# V_6.net
KiCad netlist of a schematic drawn in Altium Designer
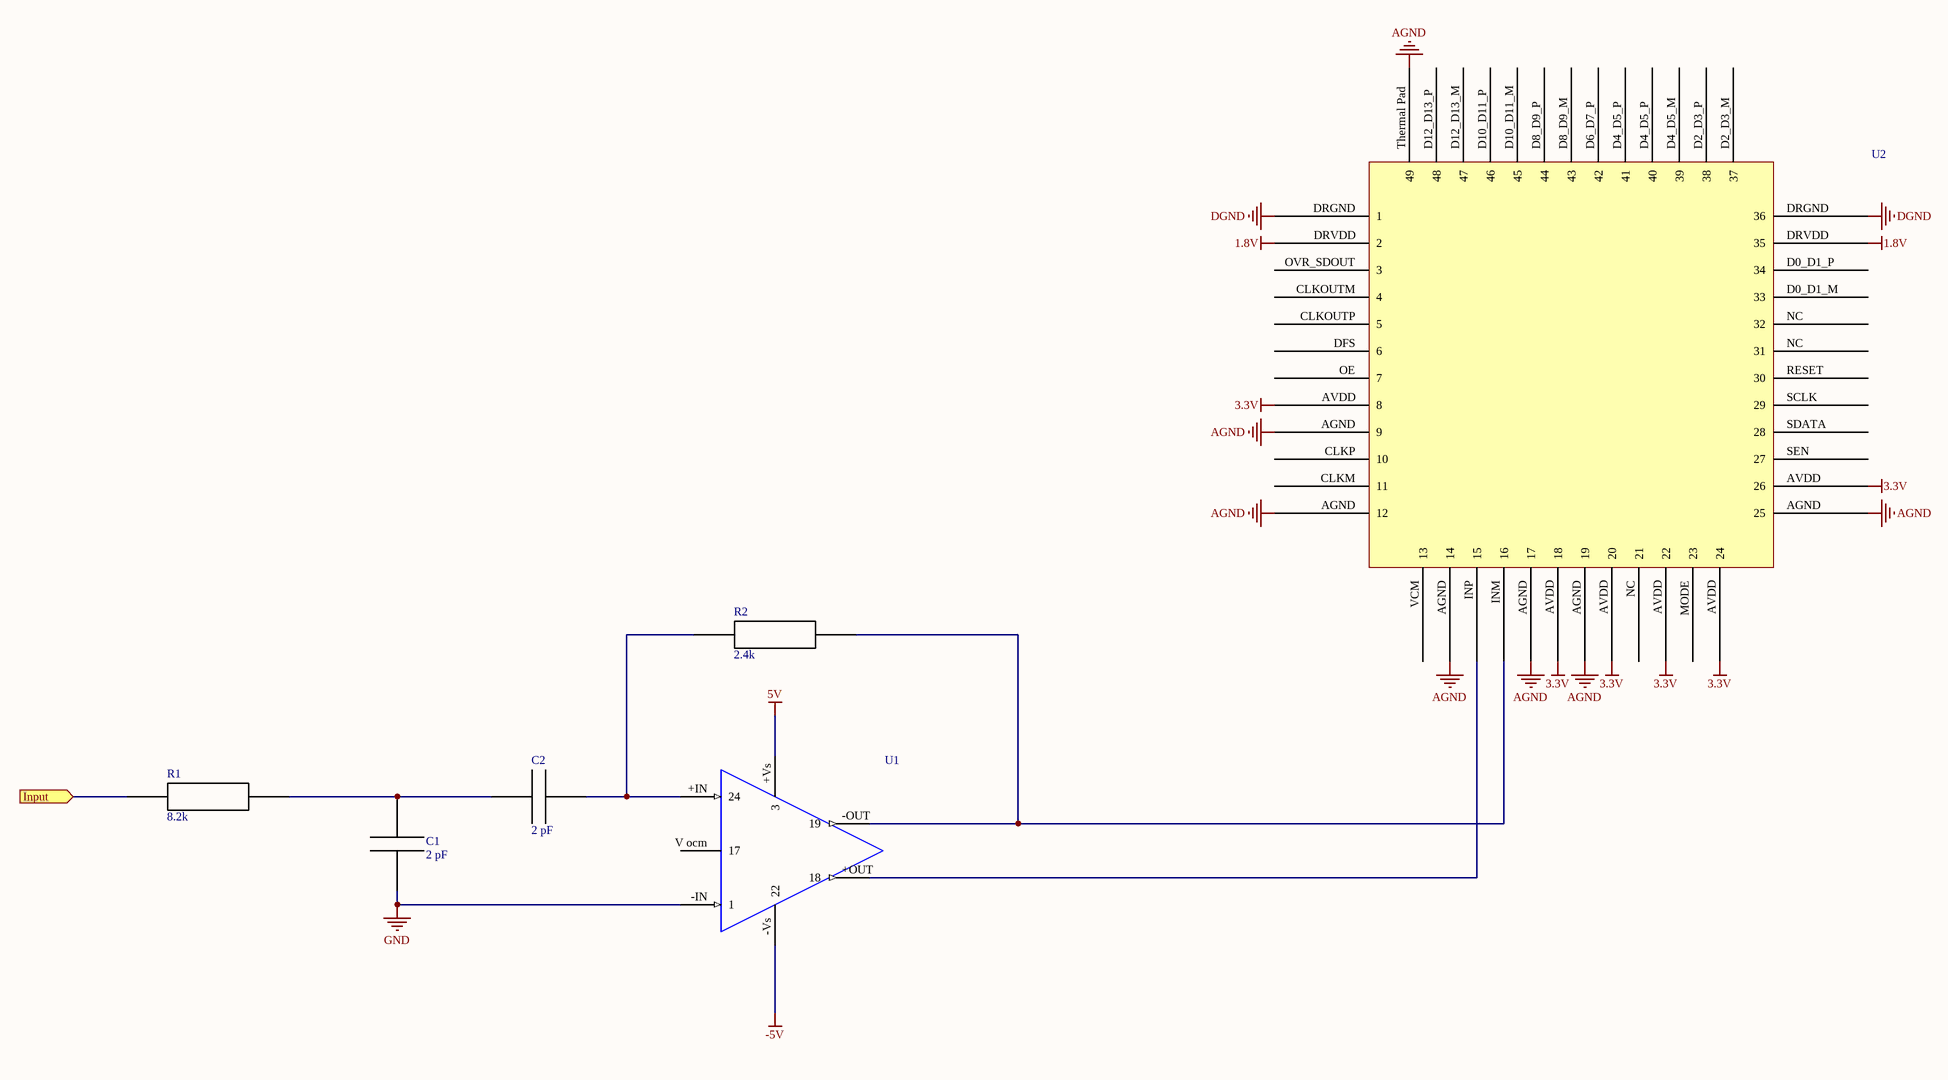
[diagram p0: V_6.SchDoc]

(export (version "E")
  (design (tool "Eeschema 10.0.6"))
  (components
    (comp (ref "C1") (value "2 pF") (footprint "C_0805") (libsource (lib "V_6") (part "C")))
    (comp (ref "C2") (value "2 pF") (footprint "C_0805") (libsource (lib "V_6") (part "C")))
    (comp (ref "R1") (value "8.2k") (libsource (lib "V_6") (part "R")))
    (comp (ref "R2") (value "2.4k") (libsource (lib "V_6") (part "R")))
    (comp (ref "U1") (value "~") (footprint "ADA4932-2") (libsource (lib "V_6") (part "ADA4932-2")))
    (comp (ref "U2") (value "~") (footprint "ADS61B49") (libsource (lib "V_6") (part "ADS61B49")))
  )
  (nets
    (net (code "1") (name "-5V") (class "Default")
      (node (ref "U1") (pin "-Vs") (pinfunction "22_-Vs") (pintype "passive"))
    )
    (net (code "2") (name "/Input") (class "Default") (node (ref "R1") (pin "1") (pintype "passive")))
    (net (code "3") (name "1.8V") (class "Default")
      (node (ref "U2") (pin "DRVDD") (pinfunction "2_DRVDD") (pintype "passive"))
    )
    (net (code "4") (name "3.3V") (class "Default")
      (node (ref "U2") (pin "AVDD") (pinfunction "8_AVDD") (pintype "passive"))
    )
    (net (code "5") (name "5V") (class "Default")
      (node (ref "U1") (pin "+Vs") (pinfunction "3_+Vs") (pintype "passive"))
    )
    (net (code "6") (name "AGND") (class "Default")
      (node (ref "U2") (pin "AGND") (pinfunction "9_AGND") (pintype "passive"))
      (node (ref "U2") (pin "Thermal_Pad") (pinfunction "49_Thermal_Pad") (pintype "passive"))
    )
    (net (code "7") (name "DGND") (class "Default")
      (node (ref "U2") (pin "DRGND") (pinfunction "1_DRGND") (pintype "passive"))
    )
    (net (code "8") (name "GND") (class "Default")
      (node (ref "C1") (pin "1") (pintype "passive"))
      (node (ref "U1") (pin "-IN") (pinfunction "1_-IN") (pintype "input"))
    )
    (net (code "9") (name "Net-(C1-Pad2)") (class "Default")
      (node (ref "C1") (pin "2") (pintype "passive"))
      (node (ref "C2") (pin "1") (pintype "passive"))
      (node (ref "R1") (pin "2") (pintype "passive"))
    )
    (net (code "10") (name "Net-(U1-18)") (class "Default")
      (node (ref "U1") (pin "+OUT") (pinfunction "18_+OUT") (pintype "output"))
      (node (ref "U2") (pin "INP") (pinfunction "15_INP") (pintype "passive"))
    )
    (net (code "11") (name "Net-(U1-19)") (class "Default")
      (node (ref "R2") (pin "2") (pintype "passive"))
      (node (ref "U1") (pin "-OUT") (pinfunction "19_-OUT") (pintype "output"))
      (node (ref "U2") (pin "INM") (pinfunction "16_INM") (pintype "passive"))
    )
    (net (code "12") (name "Net-(U1-24)") (class "Default")
      (node (ref "C2") (pin "2") (pintype "passive"))
      (node (ref "R2") (pin "1") (pintype "passive"))
      (node (ref "U1") (pin "+IN") (pinfunction "24_+IN") (pintype "input"))
    )
    (net (code "13") (name "unconnected-(U1-17-PadV_ocm)") (class "Default")
      (node (ref "U1") (pin "V_ocm") (pinfunction "17_V_ocm") (pintype "passive"))
    )
    (net (code "14") (name "unconnected-(U2-3-PadOVR_SDOUT)") (class "Default")
      (node (ref "U2") (pin "OVR_SDOUT") (pinfunction "3_OVR_SDOUT") (pintype "passive"))
    )
    (net (code "15") (name "unconnected-(U2-4-PadCLKOUTM)") (class "Default")
      (node (ref "U2") (pin "CLKOUTM") (pinfunction "4_CLKOUTM") (pintype "passive"))
    )
    (net (code "16") (name "unconnected-(U2-5-PadCLKOUTP)") (class "Default")
      (node (ref "U2") (pin "CLKOUTP") (pinfunction "5_CLKOUTP") (pintype "passive"))
    )
    (net (code "17") (name "unconnected-(U2-6-PadDFS)") (class "Default")
      (node (ref "U2") (pin "DFS") (pinfunction "6_DFS") (pintype "passive"))
    )
    (net (code "18") (name "unconnected-(U2-7-PadOE)") (class "Default")
      (node (ref "U2") (pin "OE") (pinfunction "7_OE") (pintype "passive"))
    )
    (net (code "19") (name "unconnected-(U2-10-PadCLKP)") (class "Default")
      (node (ref "U2") (pin "CLKP") (pinfunction "10_CLKP") (pintype "passive"))
    )
    (net (code "20") (name "unconnected-(U2-11-PadCLKM)") (class "Default")
      (node (ref "U2") (pin "CLKM") (pinfunction "11_CLKM") (pintype "passive"))
    )
    (net (code "21") (name "unconnected-(U2-13-PadVCM)") (class "Default")
      (node (ref "U2") (pin "VCM") (pinfunction "13_VCM") (pintype "passive"))
    )
    (net (code "22") (name "unconnected-(U2-21-PadNC)") (class "Default")
      (node (ref "U2") (pin "NC") (pinfunction "21_NC") (pintype "passive"))
    )
    (net (code "23") (name "unconnected-(U2-23-PadMODE)") (class "Default")
      (node (ref "U2") (pin "MODE") (pinfunction "23_MODE") (pintype "passive"))
    )
    (net (code "24") (name "unconnected-(U2-27-PadSEN)") (class "Default")
      (node (ref "U2") (pin "SEN") (pinfunction "27_SEN") (pintype "passive"))
    )
    (net (code "25") (name "unconnected-(U2-28-PadSDATA)") (class "Default")
      (node (ref "U2") (pin "SDATA") (pinfunction "28_SDATA") (pintype "passive"))
    )
    (net (code "26") (name "unconnected-(U2-29-PadSCLK)") (class "Default")
      (node (ref "U2") (pin "SCLK") (pinfunction "29_SCLK") (pintype "passive"))
    )
    (net (code "27") (name "unconnected-(U2-30-PadRESET)") (class "Default")
      (node (ref "U2") (pin "RESET") (pinfunction "30_RESET") (pintype "passive"))
    )
    (net (code "28") (name "unconnected-(U2-31-PadNC)") (class "Default")
      (node (ref "U2") (pin "NC") (pinfunction "31_NC") (pintype "passive"))
    )
    (net (code "29") (name "unconnected-(U2-32-PadNC)") (class "Default")
      (node (ref "U2") (pin "NC") (pinfunction "32_NC") (pintype "passive"))
    )
    (net (code "30") (name "unconnected-(U2-33-PadD0_D1_M)") (class "Default")
      (node (ref "U2") (pin "D0_D1_M") (pinfunction "33_D0_D1_M") (pintype "passive"))
    )
    (net (code "31") (name "unconnected-(U2-34-PadD0_D1_P)") (class "Default")
      (node (ref "U2") (pin "D0_D1_P") (pinfunction "34_D0_D1_P") (pintype "passive"))
    )
    (net (code "32") (name "unconnected-(U2-37-PadD2_D3_M)") (class "Default")
      (node (ref "U2") (pin "D2_D3_M") (pinfunction "37_D2_D3_M") (pintype "passive"))
    )
    (net (code "33") (name "unconnected-(U2-38-PadD2_D3_P)") (class "Default")
      (node (ref "U2") (pin "D2_D3_P") (pinfunction "38_D2_D3_P") (pintype "passive"))
    )
    (net (code "34") (name "unconnected-(U2-39-PadD4_D5_M)") (class "Default")
      (node (ref "U2") (pin "D4_D5_M") (pinfunction "39_D4_D5_M") (pintype "passive"))
    )
    (net (code "35") (name "unconnected-(U2-40-PadD4_D5_P)") (class "Default")
      (node (ref "U2") (pin "D4_D5_P") (pinfunction "40_D4_D5_P") (pintype "passive"))
    )
    (net (code "36") (name "unconnected-(U2-41-PadD4_D5_P)") (class "Default")
      (node (ref "U2") (pin "D4_D5_P") (pinfunction "41_D4_D5_P") (pintype "passive"))
    )
    (net (code "37") (name "unconnected-(U2-42-PadD6_D7_P)") (class "Default")
      (node (ref "U2") (pin "D6_D7_P") (pinfunction "42_D6_D7_P") (pintype "passive"))
    )
    (net (code "38") (name "unconnected-(U2-43-PadD8_D9_M)") (class "Default")
      (node (ref "U2") (pin "D8_D9_M") (pinfunction "43_D8_D9_M") (pintype "passive"))
    )
    (net (code "39") (name "unconnected-(U2-44-PadD8_D9_P)") (class "Default")
      (node (ref "U2") (pin "D8_D9_P") (pinfunction "44_D8_D9_P") (pintype "passive"))
    )
    (net (code "40") (name "unconnected-(U2-45-PadD10_D11_M)") (class "Default")
      (node (ref "U2") (pin "D10_D11_M") (pinfunction "45_D10_D11_M") (pintype "passive"))
    )
    (net (code "41") (name "unconnected-(U2-46-PadD10_D11_P)") (class "Default")
      (node (ref "U2") (pin "D10_D11_P") (pinfunction "46_D10_D11_P") (pintype "passive"))
    )
    (net (code "42") (name "unconnected-(U2-47-PadD12_D13_M)") (class "Default")
      (node (ref "U2") (pin "D12_D13_M") (pinfunction "47_D12_D13_M") (pintype "passive"))
    )
    (net (code "43") (name "unconnected-(U2-48-PadD12_D13_P)") (class "Default")
      (node (ref "U2") (pin "D12_D13_P") (pinfunction "48_D12_D13_P") (pintype "passive"))
    )
  )
)
